# CANConnectors.net
KiCad netlist of a schematic drawn in Altium Designer
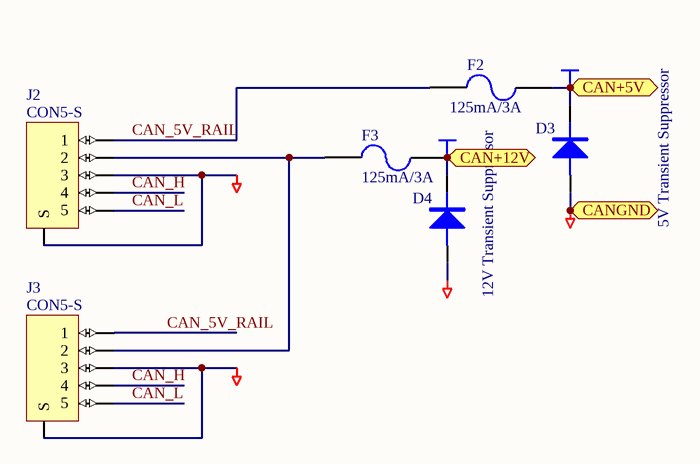
[diagram p0: CANConnectors.SCHDOC]

(export (version "E")
  (design (tool "Eeschema 10.0.6"))
  (components
    (comp (ref "D3")
      (value "5V Transient Suppressor")
      (footprint "SMA")
      (description "Diode")
      (libsource (lib "RCLDQ") (part "DIODE"))
    )
    (comp (ref "D4")
      (value "12V Transient Suppressor")
      (footprint "SMA")
      (description "Diode")
      (libsource (lib "RCLDQ") (part "DIODE"))
    )
    (comp (ref "F2")
      (value "125mA/3A")
      (footprint "LITTELFUSE-154")
      (description "Fuse")
      (libsource (lib "*") (part "FUSE2"))
    )
    (comp (ref "F3")
      (value "125mA/3A")
      (footprint "LITTELFUSE-154")
      (description "Fuse")
      (libsource (lib "*") (part "FUSE2"))
    )
    (comp (ref "J2")
      (value "CON5-S")
      (footprint "TRIAD5F")
      (description "Connector, 2 pin, with shield @ S")
      (libsource (lib "*") (part "CON5-S"))
    )
    (comp (ref "J3")
      (value "CON5-S")
      (footprint "TRIAD5F")
      (description "Connector, 2 pin, with shield @ S")
      (libsource (lib "*") (part "CON5-S"))
    )
  )
  (nets
    (net (code "1") (name "/CAN_5V_RAIL") (class "Default")
      (node (ref "F2") (pin "1") (pinfunction "1_1") (pintype "passive"))
      (node (ref "J2") (pin "1") (pinfunction "1_1") (pintype "bidirectional"))
      (node (ref "J3") (pin "1") (pinfunction "1_1") (pintype "bidirectional"))
    )
    (net (code "2") (name "/CAN_H") (class "Default")
      (node (ref "J2") (pin "4") (pinfunction "4_4") (pintype "bidirectional"))
      (node (ref "J3") (pin "4") (pinfunction "4_4") (pintype "bidirectional"))
    )
    (net (code "3") (name "/CAN_L") (class "Default")
      (node (ref "J2") (pin "5") (pinfunction "5_5") (pintype "bidirectional"))
      (node (ref "J3") (pin "5") (pinfunction "5_5") (pintype "bidirectional"))
    )
    (net (code "4") (name "CAN+5V") (class "Default")
      (node (ref "D3") (pin "K") (pinfunction "K_K") (pintype "passive"))
      (node (ref "F2") (pin "2") (pinfunction "2_2") (pintype "passive"))
    )
    (net (code "5") (name "CAN+12V") (class "Default")
      (node (ref "D4") (pin "K") (pinfunction "K_K") (pintype "passive"))
      (node (ref "F3") (pin "2") (pinfunction "2_2") (pintype "passive"))
    )
    (net (code "6") (name "CANGND") (class "Default")
      (node (ref "D3") (pin "A") (pinfunction "A_A") (pintype "passive"))
      (node (ref "D4") (pin "A") (pinfunction "A_A") (pintype "passive"))
      (node (ref "J2") (pin "0") (pinfunction "S_0") (pintype "bidirectional"))
      (node (ref "J2") (pin "3") (pinfunction "3_3") (pintype "bidirectional"))
      (node (ref "J3") (pin "0") (pinfunction "S_0") (pintype "bidirectional"))
      (node (ref "J3") (pin "3") (pinfunction "3_3") (pintype "bidirectional"))
    )
    (net (code "7") (name "Net-(F3-Pad1)") (class "Default")
      (node (ref "F3") (pin "1") (pinfunction "1_1") (pintype "passive"))
      (node (ref "J2") (pin "2") (pinfunction "2_2") (pintype "bidirectional"))
      (node (ref "J3") (pin "2") (pinfunction "2_2") (pintype "bidirectional"))
    )
  )
)
